# Optocoupler_Interface.net
KiCad netlist of a schematic drawn in Altium Designer
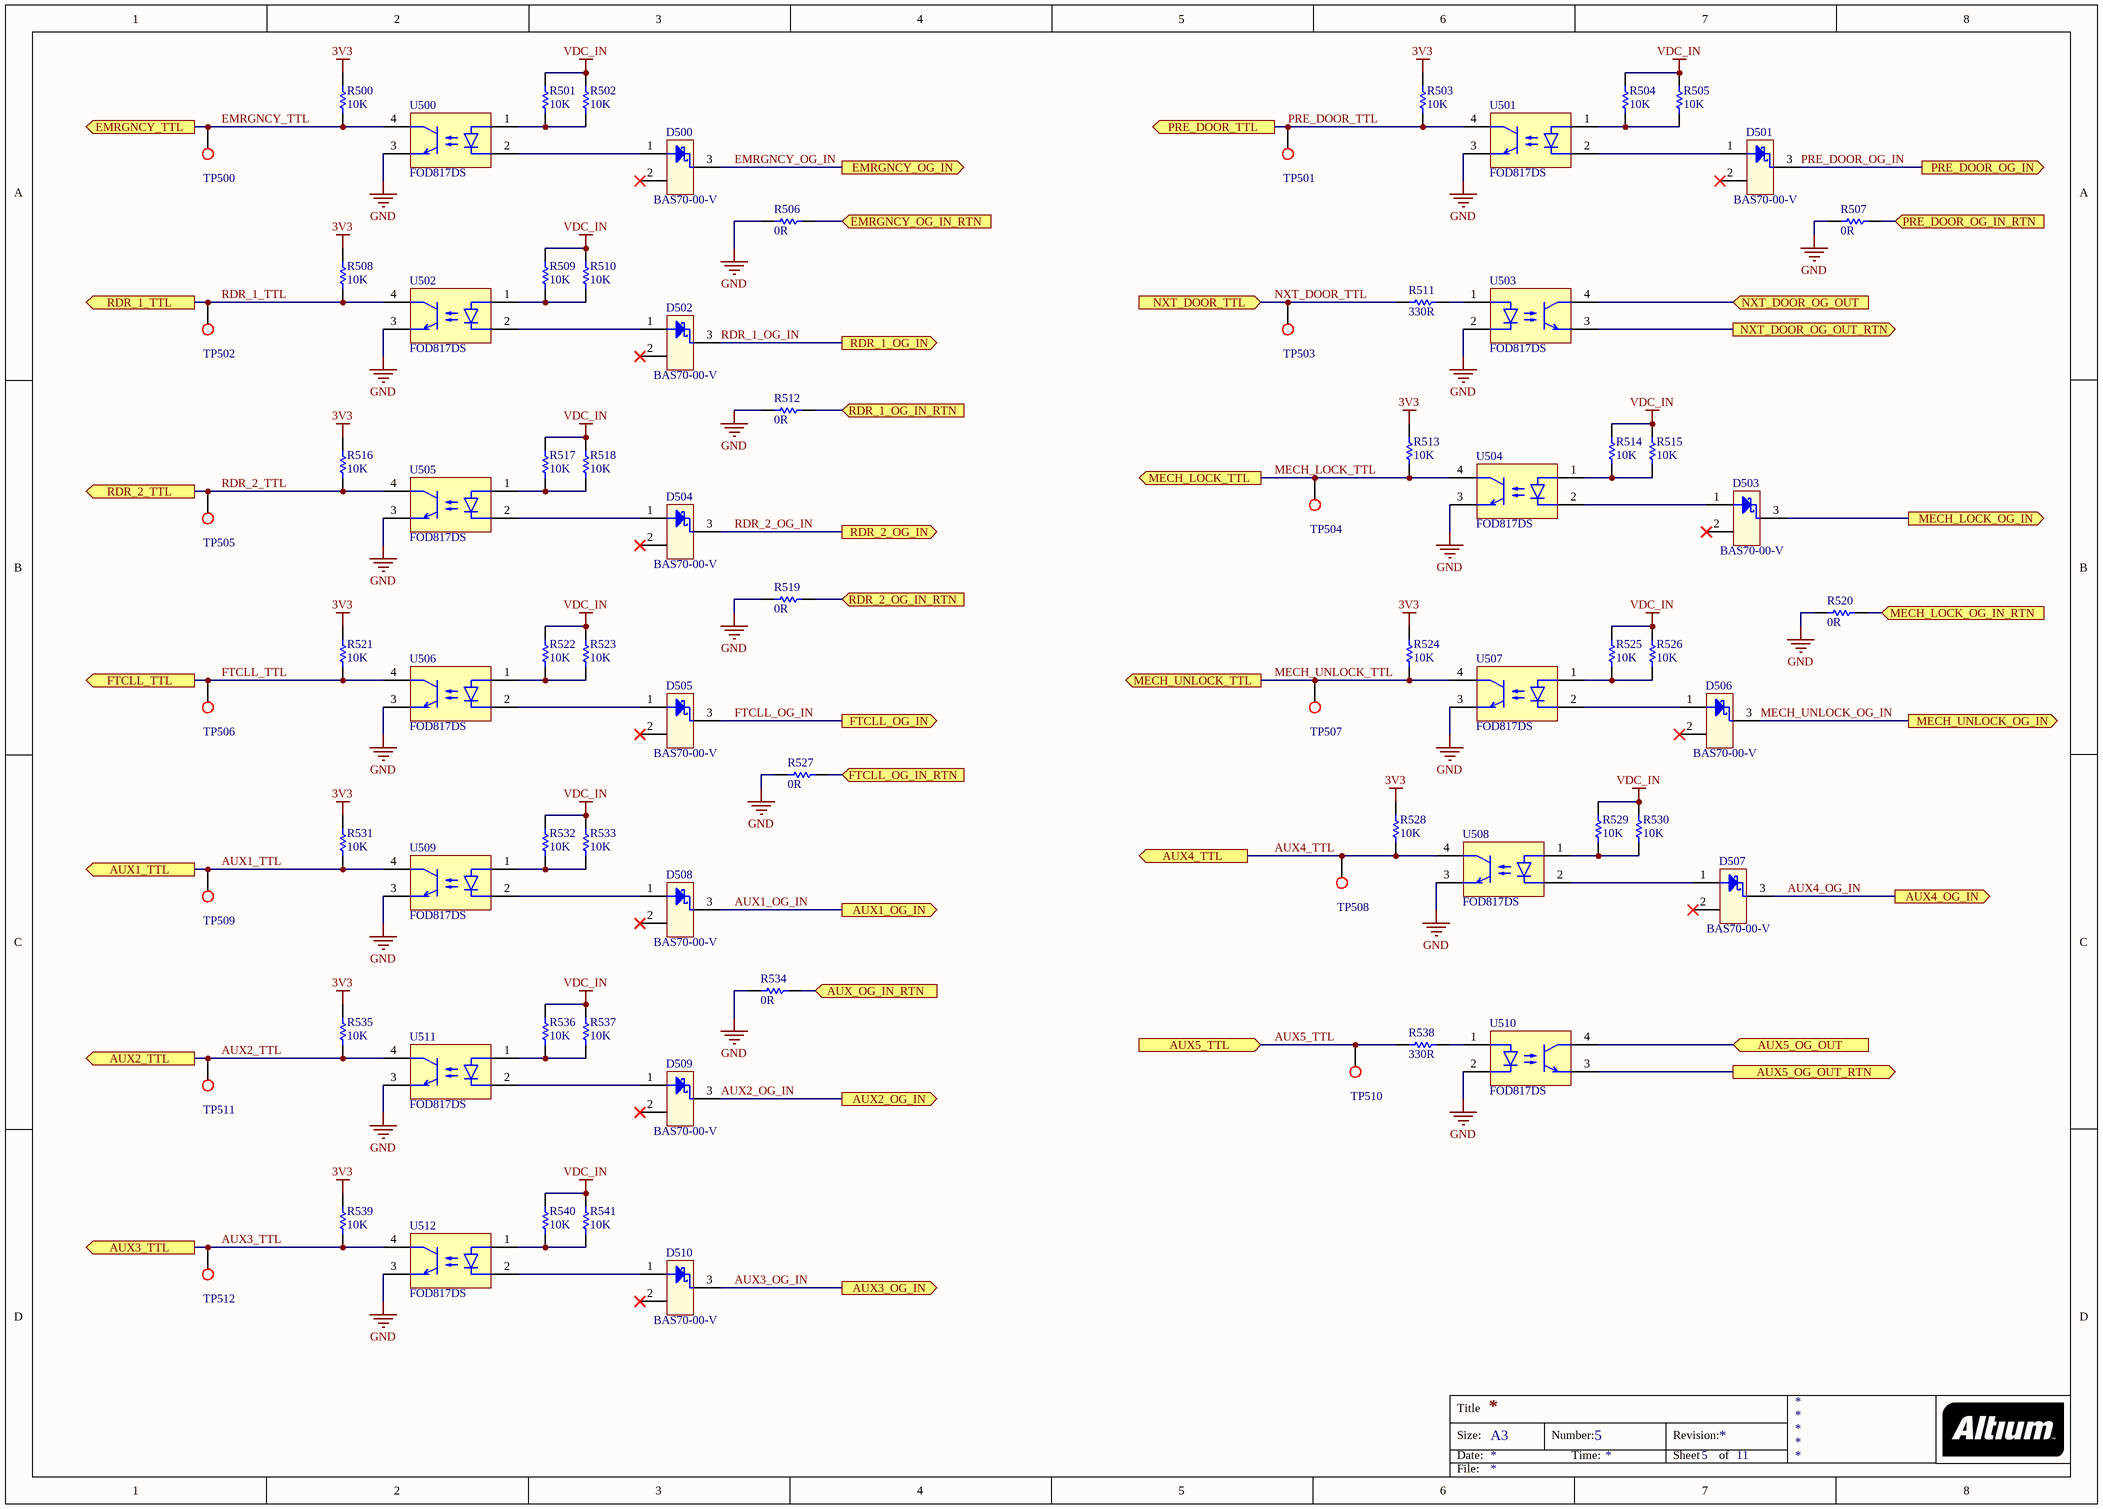
[diagram p0: Optocoupler_Interface.SchDoc]

(export (version "E")
  (design (tool "Eeschema 10.0.6"))
  (components
    (comp (ref "D500")
      (value "BAS70-00-V")
      (footprint "SOT90P247X115-3N")
      (description "Diode, Schottky, 0.41V @1mA, BAS70-00-V, SOT23")
      (fields (field (name "MANUFACTURER") "VISHAY"))
      (libsource (lib "Anime_Semiconductor") (part "AS15-820M-SI20-0002"))
    )
    (comp (ref "D501")
      (value "BAS70-00-V")
      (footprint "SOT90P247X115-3N")
      (description "Diode, Schottky, 0.41V @1mA, BAS70-00-V, SOT23")
      (fields (field (name "MANUFACTURER") "VISHAY"))
      (libsource (lib "Anime_Semiconductor") (part "AS15-820M-SI20-0002"))
    )
    (comp (ref "D502")
      (value "BAS70-00-V")
      (footprint "SOT90P247X115-3N")
      (description "Diode, Schottky, 0.41V @1mA, BAS70-00-V, SOT23")
      (fields (field (name "MANUFACTURER") "VISHAY"))
      (libsource (lib "Anime_Semiconductor") (part "AS15-820M-SI20-0002"))
    )
    (comp (ref "D503")
      (value "BAS70-00-V")
      (footprint "SOT90P247X115-3N")
      (description "Diode, Schottky, 0.41V @1mA, BAS70-00-V, SOT23")
      (fields (field (name "MANUFACTURER") "VISHAY"))
      (libsource (lib "Anime_Semiconductor") (part "AS15-820M-SI20-0002"))
    )
    (comp (ref "D504")
      (value "BAS70-00-V")
      (footprint "SOT90P247X115-3N")
      (description "Diode, Schottky, 0.41V @1mA, BAS70-00-V, SOT23")
      (fields (field (name "MANUFACTURER") "VISHAY"))
      (libsource (lib "Anime_Semiconductor") (part "AS15-820M-SI20-0002"))
    )
    (comp (ref "D505")
      (value "BAS70-00-V")
      (footprint "SOT90P247X115-3N")
      (description "Diode, Schottky, 0.41V @1mA, BAS70-00-V, SOT23")
      (fields (field (name "MANUFACTURER") "VISHAY"))
      (libsource (lib "Anime_Semiconductor") (part "AS15-820M-SI20-0002"))
    )
    (comp (ref "D506")
      (value "BAS70-00-V")
      (footprint "SOT90P247X115-3N")
      (description "Diode, Schottky, 0.41V @1mA, BAS70-00-V, SOT23")
      (fields (field (name "MANUFACTURER") "VISHAY"))
      (libsource (lib "Anime_Semiconductor") (part "AS15-820M-SI20-0002"))
    )
    (comp (ref "D507")
      (value "BAS70-00-V")
      (footprint "SOT90P247X115-3N")
      (description "Diode, Schottky, 0.41V @1mA, BAS70-00-V, SOT23")
      (fields (field (name "MANUFACTURER") "VISHAY"))
      (libsource (lib "Anime_Semiconductor") (part "AS15-820M-SI20-0002"))
    )
    (comp (ref "D508")
      (value "BAS70-00-V")
      (footprint "SOT90P247X115-3N")
      (description "Diode, Schottky, 0.41V @1mA, BAS70-00-V, SOT23")
      (fields (field (name "MANUFACTURER") "VISHAY"))
      (libsource (lib "Anime_Semiconductor") (part "AS15-820M-SI20-0002"))
    )
    (comp (ref "D509")
      (value "BAS70-00-V")
      (footprint "SOT90P247X115-3N")
      (description "Diode, Schottky, 0.41V @1mA, BAS70-00-V, SOT23")
      (fields (field (name "MANUFACTURER") "VISHAY"))
      (libsource (lib "Anime_Semiconductor") (part "AS15-820M-SI20-0002"))
    )
    (comp (ref "D510")
      (value "BAS70-00-V")
      (footprint "SOT90P247X115-3N")
      (description "Diode, Schottky, 0.41V @1mA, BAS70-00-V, SOT23")
      (fields (field (name "MANUFACTURER") "VISHAY"))
      (libsource (lib "Anime_Semiconductor") (part "AS15-820M-SI20-0002"))
    )
    (comp (ref "R500")
      (value "10K")
      (footprint "RESC1005X04N")
      (description "RES, E24, Thick Film, SMD, 10K, 1%, 0.1W, 0402")
      (fields
        (field (name "MANUFACTURER") "Panasonic")
        (field (name "MANUFACTURER PART NUMBER") "ERJ-2RKF1002X")
      )
      (libsource (lib "Anime_Resistor") (part "AR19-4100-S2B2-0000"))
    )
    (comp (ref "R501")
      (value "10K")
      (footprint "RESC2012X07N")
      (description "RES, E24, Thick Film, SMD, 10K, 1%, 0.125W, 0805")
      (fields
        (field (name "MANUFACTURER") "Panasonic")
        (field (name "MANUFACTURER PART NUMBER") "ERJ-6ENF1002V")
      )
      (libsource (lib "Anime_Resistor") (part "AR19-4100-S4B2-0000"))
    )
    (comp (ref "R502")
      (value "10K")
      (footprint "RESC2012X07N")
      (description "RES, E24, Thick Film, SMD, 10K, 1%, 0.125W, 0805")
      (fields
        (field (name "MANUFACTURER") "Panasonic")
        (field (name "MANUFACTURER PART NUMBER") "ERJ-6ENF1002V")
      )
      (libsource (lib "Anime_Resistor") (part "AR19-4100-S4B2-0000"))
    )
    (comp (ref "R503")
      (value "10K")
      (footprint "RESC1005X04N")
      (description "RES, E24, Thick Film, SMD, 10K, 1%, 0.1W, 0402")
      (fields
        (field (name "MANUFACTURER") "Panasonic")
        (field (name "MANUFACTURER PART NUMBER") "ERJ-2RKF1002X")
      )
      (libsource (lib "Anime_Resistor") (part "AR19-4100-S2B2-0000"))
    )
    (comp (ref "R504")
      (value "10K")
      (footprint "RESC2012X07N")
      (description "RES, E24, Thick Film, SMD, 10K, 1%, 0.125W, 0805")
      (fields
        (field (name "MANUFACTURER") "Panasonic")
        (field (name "MANUFACTURER PART NUMBER") "ERJ-6ENF1002V")
      )
      (libsource (lib "Anime_Resistor") (part "AR19-4100-S4B2-0000"))
    )
    (comp (ref "R505")
      (value "10K")
      (footprint "RESC2012X07N")
      (description "RES, E24, Thick Film, SMD, 10K, 1%, 0.125W, 0805")
      (fields
        (field (name "MANUFACTURER") "Panasonic")
        (field (name "MANUFACTURER PART NUMBER") "ERJ-6ENF1002V")
      )
      (libsource (lib "Anime_Resistor") (part "AR19-4100-S4B2-0000"))
    )
    (comp (ref "R506")
      (value "0R")
      (footprint "RESC2012X07N")
      (description "RES, Thick Film, SMD, 0R, Jumper, 0.125W, 0805")
      (fields
        (field (name "MANUFACTURER") "Panasonic")
        (field (name "MANUFACTURER PART NUMBER") "ERJ-6GEY0R00V")
      )
      (libsource (lib "Anime_Resistor") (part "AR19-0000-S407-0000"))
    )
    (comp (ref "R507")
      (value "0R")
      (footprint "RESC2012X07N")
      (description "RES, Thick Film, SMD, 0R, Jumper, 0.125W, 0805")
      (fields
        (field (name "MANUFACTURER") "Panasonic")
        (field (name "MANUFACTURER PART NUMBER") "ERJ-6GEY0R00V")
      )
      (libsource (lib "Anime_Resistor") (part "AR19-0000-S407-0000"))
    )
    (comp (ref "R508")
      (value "10K")
      (footprint "RESC1005X04N")
      (description "RES, E24, Thick Film, SMD, 10K, 1%, 0.1W, 0402")
      (fields
        (field (name "MANUFACTURER") "Panasonic")
        (field (name "MANUFACTURER PART NUMBER") "ERJ-2RKF1002X")
      )
      (libsource (lib "Anime_Resistor") (part "AR19-4100-S2B2-0000"))
    )
    (comp (ref "R509")
      (value "10K")
      (footprint "RESC2012X07N")
      (description "RES, E24, Thick Film, SMD, 10K, 1%, 0.125W, 0805")
      (fields
        (field (name "MANUFACTURER") "Panasonic")
        (field (name "MANUFACTURER PART NUMBER") "ERJ-6ENF1002V")
      )
      (libsource (lib "Anime_Resistor") (part "AR19-4100-S4B2-0000"))
    )
    (comp (ref "R510")
      (value "10K")
      (footprint "RESC2012X07N")
      (description "RES, E24, Thick Film, SMD, 10K, 1%, 0.125W, 0805")
      (fields
        (field (name "MANUFACTURER") "Panasonic")
        (field (name "MANUFACTURER PART NUMBER") "ERJ-6ENF1002V")
      )
      (libsource (lib "Anime_Resistor") (part "AR19-4100-S4B2-0000"))
    )
    (comp (ref "R511")
      (value "330R")
      (footprint "RESC1005X04N")
      (description "RES, E24, Thick Film, SMD, 330R, 1%, 0.1W, 0402")
      (fields
        (field (name "MANUFACTURER") "Panasonic")
        (field (name "MANUFACTURER PART NUMBER") "ERJ-2RKF3300X")
      )
      (libsource (lib "Anime_Resistor") (part "AR19-2330-S2B2-0000"))
    )
    (comp (ref "R512")
      (value "0R")
      (footprint "RESC2012X07N")
      (description "RES, Thick Film, SMD, 0R, Jumper, 0.125W, 0805")
      (fields
        (field (name "MANUFACTURER") "Panasonic")
        (field (name "MANUFACTURER PART NUMBER") "ERJ-6GEY0R00V")
      )
      (libsource (lib "Anime_Resistor") (part "AR19-0000-S407-0000"))
    )
    (comp (ref "R513")
      (value "10K")
      (footprint "RESC1005X04N")
      (description "RES, E24, Thick Film, SMD, 10K, 1%, 0.1W, 0402")
      (fields
        (field (name "MANUFACTURER") "Panasonic")
        (field (name "MANUFACTURER PART NUMBER") "ERJ-2RKF1002X")
      )
      (libsource (lib "Anime_Resistor") (part "AR19-4100-S2B2-0000"))
    )
    (comp (ref "R514")
      (value "10K")
      (footprint "RESC2012X07N")
      (description "RES, E24, Thick Film, SMD, 10K, 1%, 0.125W, 0805")
      (fields
        (field (name "MANUFACTURER") "Panasonic")
        (field (name "MANUFACTURER PART NUMBER") "ERJ-6ENF1002V")
      )
      (libsource (lib "Anime_Resistor") (part "AR19-4100-S4B2-0000"))
    )
    (comp (ref "R515")
      (value "10K")
      (footprint "RESC2012X07N")
      (description "RES, E24, Thick Film, SMD, 10K, 1%, 0.125W, 0805")
      (fields
        (field (name "MANUFACTURER") "Panasonic")
        (field (name "MANUFACTURER PART NUMBER") "ERJ-6ENF1002V")
      )
      (libsource (lib "Anime_Resistor") (part "AR19-4100-S4B2-0000"))
    )
    (comp (ref "R516")
      (value "10K")
      (footprint "RESC1005X04N")
      (description "RES, E24, Thick Film, SMD, 10K, 1%, 0.1W, 0402")
      (fields
        (field (name "MANUFACTURER") "Panasonic")
        (field (name "MANUFACTURER PART NUMBER") "ERJ-2RKF1002X")
      )
      (libsource (lib "Anime_Resistor") (part "AR19-4100-S2B2-0000"))
    )
    (comp (ref "R517")
      (value "10K")
      (footprint "RESC2012X07N")
      (description "RES, E24, Thick Film, SMD, 10K, 1%, 0.125W, 0805")
      (fields
        (field (name "MANUFACTURER") "Panasonic")
        (field (name "MANUFACTURER PART NUMBER") "ERJ-6ENF1002V")
      )
      (libsource (lib "Anime_Resistor") (part "AR19-4100-S4B2-0000"))
    )
    (comp (ref "R518")
      (value "10K")
      (footprint "RESC2012X07N")
      (description "RES, E24, Thick Film, SMD, 10K, 1%, 0.125W, 0805")
      (fields
        (field (name "MANUFACTURER") "Panasonic")
        (field (name "MANUFACTURER PART NUMBER") "ERJ-6ENF1002V")
      )
      (libsource (lib "Anime_Resistor") (part "AR19-4100-S4B2-0000"))
    )
    (comp (ref "R519")
      (value "0R")
      (footprint "RESC2012X07N")
      (description "RES, Thick Film, SMD, 0R, Jumper, 0.125W, 0805")
      (fields
        (field (name "MANUFACTURER") "Panasonic")
        (field (name "MANUFACTURER PART NUMBER") "ERJ-6GEY0R00V")
      )
      (libsource (lib "Anime_Resistor") (part "AR19-0000-S407-0000"))
    )
    (comp (ref "R520")
      (value "0R")
      (footprint "RESC2012X07N")
      (description "RES, Thick Film, SMD, 0R, Jumper, 0.125W, 0805")
      (fields
        (field (name "MANUFACTURER") "Panasonic")
        (field (name "MANUFACTURER PART NUMBER") "ERJ-6GEY0R00V")
      )
      (libsource (lib "Anime_Resistor") (part "AR19-0000-S407-0000"))
    )
    (comp (ref "R521")
      (value "10K")
      (footprint "RESC1005X04N")
      (description "RES, E24, Thick Film, SMD, 10K, 1%, 0.1W, 0402")
      (fields
        (field (name "MANUFACTURER") "Panasonic")
        (field (name "MANUFACTURER PART NUMBER") "ERJ-2RKF1002X")
      )
      (libsource (lib "Anime_Resistor") (part "AR19-4100-S2B2-0000"))
    )
    (comp (ref "R522")
      (value "10K")
      (footprint "RESC2012X07N")
      (description "RES, E24, Thick Film, SMD, 10K, 1%, 0.125W, 0805")
      (fields
        (field (name "MANUFACTURER") "Panasonic")
        (field (name "MANUFACTURER PART NUMBER") "ERJ-6ENF1002V")
      )
      (libsource (lib "Anime_Resistor") (part "AR19-4100-S4B2-0000"))
    )
    (comp (ref "R523")
      (value "10K")
      (footprint "RESC2012X07N")
      (description "RES, E24, Thick Film, SMD, 10K, 1%, 0.125W, 0805")
      (fields
        (field (name "MANUFACTURER") "Panasonic")
        (field (name "MANUFACTURER PART NUMBER") "ERJ-6ENF1002V")
      )
      (libsource (lib "Anime_Resistor") (part "AR19-4100-S4B2-0000"))
    )
    (comp (ref "R524")
      (value "10K")
      (footprint "RESC1005X04N")
      (description "RES, E24, Thick Film, SMD, 10K, 1%, 0.1W, 0402")
      (fields
        (field (name "MANUFACTURER") "Panasonic")
        (field (name "MANUFACTURER PART NUMBER") "ERJ-2RKF1002X")
      )
      (libsource (lib "Anime_Resistor") (part "AR19-4100-S2B2-0000"))
    )
    (comp (ref "R525")
      (value "10K")
      (footprint "RESC2012X07N")
      (description "RES, E24, Thick Film, SMD, 10K, 1%, 0.125W, 0805")
      (fields
        (field (name "MANUFACTURER") "Panasonic")
        (field (name "MANUFACTURER PART NUMBER") "ERJ-6ENF1002V")
      )
      (libsource (lib "Anime_Resistor") (part "AR19-4100-S4B2-0000"))
    )
    (comp (ref "R526")
      (value "10K")
      (footprint "RESC2012X07N")
      (description "RES, E24, Thick Film, SMD, 10K, 1%, 0.125W, 0805")
      (fields
        (field (name "MANUFACTURER") "Panasonic")
        (field (name "MANUFACTURER PART NUMBER") "ERJ-6ENF1002V")
      )
      (libsource (lib "Anime_Resistor") (part "AR19-4100-S4B2-0000"))
    )
    (comp (ref "R527")
      (value "0R")
      (footprint "RESC2012X07N")
      (description "RES, Thick Film, SMD, 0R, Jumper, 0.125W, 0805")
      (fields
        (field (name "MANUFACTURER") "Panasonic")
        (field (name "MANUFACTURER PART NUMBER") "ERJ-6GEY0R00V")
      )
      (libsource (lib "Anime_Resistor") (part "AR19-0000-S407-0000"))
    )
    (comp (ref "R528")
      (value "10K")
      (footprint "RESC1005X04N")
      (description "RES, E24, Thick Film, SMD, 10K, 1%, 0.1W, 0402")
      (fields
        (field (name "MANUFACTURER") "Panasonic")
        (field (name "MANUFACTURER PART NUMBER") "ERJ-2RKF1002X")
      )
      (libsource (lib "Anime_Resistor") (part "AR19-4100-S2B2-0000"))
    )
    (comp (ref "R529")
      (value "10K")
      (footprint "RESC2012X07N")
      (description "RES, E24, Thick Film, SMD, 10K, 1%, 0.125W, 0805")
      (fields
        (field (name "MANUFACTURER") "Panasonic")
        (field (name "MANUFACTURER PART NUMBER") "ERJ-6ENF1002V")
      )
      (libsource (lib "Anime_Resistor") (part "AR19-4100-S4B2-0000"))
    )
    (comp (ref "R530")
      (value "10K")
      (footprint "RESC2012X07N")
      (description "RES, E24, Thick Film, SMD, 10K, 1%, 0.125W, 0805")
      (fields
        (field (name "MANUFACTURER") "Panasonic")
        (field (name "MANUFACTURER PART NUMBER") "ERJ-6ENF1002V")
      )
      (libsource (lib "Anime_Resistor") (part "AR19-4100-S4B2-0000"))
    )
    (comp (ref "R531")
      (value "10K")
      (footprint "RESC1005X04N")
      (description "RES, E24, Thick Film, SMD, 10K, 1%, 0.1W, 0402")
      (fields
        (field (name "MANUFACTURER") "Panasonic")
        (field (name "MANUFACTURER PART NUMBER") "ERJ-2RKF1002X")
      )
      (libsource (lib "Anime_Resistor") (part "AR19-4100-S2B2-0000"))
    )
    (comp (ref "R532")
      (value "10K")
      (footprint "RESC2012X07N")
      (description "RES, E24, Thick Film, SMD, 10K, 1%, 0.125W, 0805")
      (fields
        (field (name "MANUFACTURER") "Panasonic")
        (field (name "MANUFACTURER PART NUMBER") "ERJ-6ENF1002V")
      )
      (libsource (lib "Anime_Resistor") (part "AR19-4100-S4B2-0000"))
    )
    (comp (ref "R533")
      (value "10K")
      (footprint "RESC2012X07N")
      (description "RES, E24, Thick Film, SMD, 10K, 1%, 0.125W, 0805")
      (fields
        (field (name "MANUFACTURER") "Panasonic")
        (field (name "MANUFACTURER PART NUMBER") "ERJ-6ENF1002V")
      )
      (libsource (lib "Anime_Resistor") (part "AR19-4100-S4B2-0000"))
    )
    (comp (ref "R534")
      (value "0R")
      (footprint "RESC2012X07N")
      (description "RES, Thick Film, SMD, 0R, Jumper, 0.125W, 0805")
      (fields
        (field (name "MANUFACTURER") "Panasonic")
        (field (name "MANUFACTURER PART NUMBER") "ERJ-6GEY0R00V")
      )
      (libsource (lib "Anime_Resistor") (part "AR19-0000-S407-0000"))
    )
    (comp (ref "R535")
      (value "10K")
      (footprint "RESC1005X04N")
      (description "RES, E24, Thick Film, SMD, 10K, 1%, 0.1W, 0402")
      (fields
        (field (name "MANUFACTURER") "Panasonic")
        (field (name "MANUFACTURER PART NUMBER") "ERJ-2RKF1002X")
      )
      (libsource (lib "Anime_Resistor") (part "AR19-4100-S2B2-0000"))
    )
    (comp (ref "R536")
      (value "10K")
      (footprint "RESC2012X07N")
      (description "RES, E24, Thick Film, SMD, 10K, 1%, 0.125W, 0805")
      (fields
        (field (name "MANUFACTURER") "Panasonic")
        (field (name "MANUFACTURER PART NUMBER") "ERJ-6ENF1002V")
      )
      (libsource (lib "Anime_Resistor") (part "AR19-4100-S4B2-0000"))
    )
    (comp (ref "R537")
      (value "10K")
      (footprint "RESC2012X07N")
      (description "RES, E24, Thick Film, SMD, 10K, 1%, 0.125W, 0805")
      (fields
        (field (name "MANUFACTURER") "Panasonic")
        (field (name "MANUFACTURER PART NUMBER") "ERJ-6ENF1002V")
      )
      (libsource (lib "Anime_Resistor") (part "AR19-4100-S4B2-0000"))
    )
    (comp (ref "R538")
      (value "330R")
      (footprint "RESC1005X04N")
      (description "RES, E24, Thick Film, SMD, 330R, 1%, 0.1W, 0402")
      (fields
        (field (name "MANUFACTURER") "Panasonic")
        (field (name "MANUFACTURER PART NUMBER") "ERJ-2RKF3300X")
      )
      (libsource (lib "Anime_Resistor") (part "AR19-2330-S2B2-0000"))
    )
    (comp (ref "R539")
      (value "10K")
      (footprint "RESC1005X04N")
      (description "RES, E24, Thick Film, SMD, 10K, 1%, 0.1W, 0402")
      (fields
        (field (name "MANUFACTURER") "Panasonic")
        (field (name "MANUFACTURER PART NUMBER") "ERJ-2RKF1002X")
      )
      (libsource (lib "Anime_Resistor") (part "AR19-4100-S2B2-0000"))
    )
    (comp (ref "R540")
      (value "10K")
      (footprint "RESC2012X07N")
      (description "RES, E24, Thick Film, SMD, 10K, 1%, 0.125W, 0805")
      (fields
        (field (name "MANUFACTURER") "Panasonic")
        (field (name "MANUFACTURER PART NUMBER") "ERJ-6ENF1002V")
      )
      (libsource (lib "Anime_Resistor") (part "AR19-4100-S4B2-0000"))
    )
    (comp (ref "R541")
      (value "10K")
      (footprint "RESC2012X07N")
      (description "RES, E24, Thick Film, SMD, 10K, 1%, 0.125W, 0805")
      (fields
        (field (name "MANUFACTURER") "Panasonic")
        (field (name "MANUFACTURER PART NUMBER") "ERJ-6ENF1002V")
      )
      (libsource (lib "Anime_Resistor") (part "AR19-4100-S4B2-0000"))
    )
    (comp (ref "TP500")
      (value "AEMT-C00S-1000-0000")
      (footprint "TP100")
      (description "Test Point, Circular, 1mm")
      (libsource (lib "Anime_Electromechanical") (part "AEMT-C00S-1000-0000"))
    )
    (comp (ref "TP501")
      (value "AEMT-C00S-1000-0000")
      (footprint "TP100")
      (description "Test Point, Circular, 1mm")
      (libsource (lib "Anime_Electromechanical") (part "AEMT-C00S-1000-0000"))
    )
    (comp (ref "TP502")
      (value "AEMT-C00S-1000-0000")
      (footprint "TP100")
      (description "Test Point, Circular, 1mm")
      (libsource (lib "Anime_Electromechanical") (part "AEMT-C00S-1000-0000"))
    )
    (comp (ref "TP503")
      (value "AEMT-C00S-1000-0000")
      (footprint "TP100")
      (description "Test Point, Circular, 1mm")
      (libsource (lib "Anime_Electromechanical") (part "AEMT-C00S-1000-0000"))
    )
    (comp (ref "TP504")
      (value "AEMT-C00S-1000-0000")
      (footprint "TP100")
      (description "Test Point, Circular, 1mm")
      (libsource (lib "Anime_Electromechanical") (part "AEMT-C00S-1000-0000"))
    )
    (comp (ref "TP505")
      (value "AEMT-C00S-1000-0000")
      (footprint "TP100")
      (description "Test Point, Circular, 1mm")
      (libsource (lib "Anime_Electromechanical") (part "AEMT-C00S-1000-0000"))
    )
    (comp (ref "TP506")
      (value "AEMT-C00S-1000-0000")
      (footprint "TP100")
      (description "Test Point, Circular, 1mm")
      (libsource (lib "Anime_Electromechanical") (part "AEMT-C00S-1000-0000"))
    )
    (comp (ref "TP507")
      (value "AEMT-C00S-1000-0000")
      (footprint "TP100")
      (description "Test Point, Circular, 1mm")
      (libsource (lib "Anime_Electromechanical") (part "AEMT-C00S-1000-0000"))
    )
    (comp (ref "TP508")
      (value "AEMT-C00S-1000-0000")
      (footprint "TP100")
      (description "Test Point, Circular, 1mm")
      (libsource (lib "Anime_Electromechanical") (part "AEMT-C00S-1000-0000"))
    )
    (comp (ref "TP509")
      (value "AEMT-C00S-1000-0000")
      (footprint "TP100")
      (description "Test Point, Circular, 1mm")
      (libsource (lib "Anime_Electromechanical") (part "AEMT-C00S-1000-0000"))
    )
    (comp (ref "TP510")
      (value "AEMT-C00S-1000-0000")
      (footprint "TP100")
      (description "Test Point, Circular, 1mm")
      (libsource (lib "Anime_Electromechanical") (part "AEMT-C00S-1000-0000"))
    )
    (comp (ref "TP511")
      (value "AEMT-C00S-1000-0000")
      (footprint "TP100")
      (description "Test Point, Circular, 1mm")
      (libsource (lib "Anime_Electromechanical") (part "AEMT-C00S-1000-0000"))
    )
    (comp (ref "TP512")
      (value "AEMT-C00S-1000-0000")
      (footprint "TP100")
      (description "Test Point, Circular, 1mm")
      (libsource (lib "Anime_Electromechanical") (part "AEMT-C00S-1000-0000"))
    )
    (comp (ref "U500")
      (value "FOD817DS")
      (footprint "SOP254P1020X400-4N")
      (description "Optocoupler, Phototransistor Output, Single Channel, CTR 300-600%, 5000V Isolation")
      (fields (field (name "MANUFACTURER") "Fairchild"))
      (libsource (lib "") (part "ASB1-850M-SM61-0000_1"))
    )
    (comp (ref "U501")
      (value "FOD817DS")
      (footprint "SOP254P1020X400-4N")
      (description "Optocoupler, Phototransistor Output, Single Channel, CTR 300-600%, 5000V Isolation")
      (fields (field (name "MANUFACTURER") "Fairchild"))
      (libsource (lib "") (part "ASB1-850M-SM61-0000_1"))
    )
    (comp (ref "U502")
      (value "FOD817DS")
      (footprint "SOP254P1020X400-4N")
      (description "Optocoupler, Phototransistor Output, Single Channel, CTR 300-600%, 5000V Isolation")
      (fields (field (name "MANUFACTURER") "Fairchild"))
      (libsource (lib "") (part "ASB1-850M-SM61-0000_1"))
    )
    (comp (ref "U503")
      (value "FOD817DS")
      (footprint "SOP254P1020X400-4N")
      (description "Optocoupler, Phototransistor Output, Single Channel, CTR 300-600%, 5000V Isolation")
      (fields (field (name "MANUFACTURER") "Fairchild"))
      (libsource (lib "Anime_Semiconductor") (part "ASB1-850M-SM61-0000"))
    )
    (comp (ref "U504")
      (value "FOD817DS")
      (footprint "SOP254P1020X400-4N")
      (description "Optocoupler, Phototransistor Output, Single Channel, CTR 300-600%, 5000V Isolation")
      (fields (field (name "MANUFACTURER") "Fairchild"))
      (libsource (lib "") (part "ASB1-850M-SM61-0000_1"))
    )
    (comp (ref "U505")
      (value "FOD817DS")
      (footprint "SOP254P1020X400-4N")
      (description "Optocoupler, Phototransistor Output, Single Channel, CTR 300-600%, 5000V Isolation")
      (fields (field (name "MANUFACTURER") "Fairchild"))
      (libsource (lib "") (part "ASB1-850M-SM61-0000_1"))
    )
    (comp (ref "U506")
      (value "FOD817DS")
      (footprint "SOP254P1020X400-4N")
      (description "Optocoupler, Phototransistor Output, Single Channel, CTR 300-600%, 5000V Isolation")
      (fields (field (name "MANUFACTURER") "Fairchild"))
      (libsource (lib "") (part "ASB1-850M-SM61-0000_1"))
    )
    (comp (ref "U507")
      (value "FOD817DS")
      (footprint "SOP254P1020X400-4N")
      (description "Optocoupler, Phototransistor Output, Single Channel, CTR 300-600%, 5000V Isolation")
      (fields (field (name "MANUFACTURER") "Fairchild"))
      (libsource (lib "") (part "ASB1-850M-SM61-0000_1"))
    )
    (comp (ref "U508")
      (value "FOD817DS")
      (footprint "SOP254P1020X400-4N")
      (description "Optocoupler, Phototransistor Output, Single Channel, CTR 300-600%, 5000V Isolation")
      (fields (field (name "MANUFACTURER") "Fairchild"))
      (libsource (lib "") (part "ASB1-850M-SM61-0000_1"))
    )
    (comp (ref "U509")
      (value "FOD817DS")
      (footprint "SOP254P1020X400-4N")
      (description "Optocoupler, Phototransistor Output, Single Channel, CTR 300-600%, 5000V Isolation")
      (fields (field (name "MANUFACTURER") "Fairchild"))
      (libsource (lib "") (part "ASB1-850M-SM61-0000_1"))
    )
    (comp (ref "U510")
      (value "FOD817DS")
      (footprint "SOP254P1020X400-4N")
      (description "Optocoupler, Phototransistor Output, Single Channel, CTR 300-600%, 5000V Isolation")
      (fields (field (name "MANUFACTURER") "Fairchild"))
      (libsource (lib "Anime_Semiconductor") (part "ASB1-850M-SM61-0000"))
    )
    (comp (ref "U511")
      (value "FOD817DS")
      (footprint "SOP254P1020X400-4N")
      (description "Optocoupler, Phototransistor Output, Single Channel, CTR 300-600%, 5000V Isolation")
      (fields (field (name "MANUFACTURER") "Fairchild"))
      (libsource (lib "") (part "ASB1-850M-SM61-0000_1"))
    )
    (comp (ref "U512")
      (value "FOD817DS")
      (footprint "SOP254P1020X400-4N")
      (description "Optocoupler, Phototransistor Output, Single Channel, CTR 300-600%, 5000V Isolation")
      (fields (field (name "MANUFACTURER") "Fairchild"))
      (libsource (lib "") (part "ASB1-850M-SM61-0000_1"))
    )
  )
  (nets
    (net (code "1") (name "/AUX1_OG_IN") (class "Default")
      (node (ref "D508") (pin "3") (pinfunction "3_3") (pintype "passive"))
    )
    (net (code "2") (name "/AUX1_TTL") (class "Default")
      (node (ref "R531") (pin "1") (pinfunction "1_1") (pintype "passive"))
      (node (ref "TP509") (pin "1") (pintype "passive"))
      (node (ref "U509") (pin "4") (pinfunction "C1_4") (pintype "passive"))
    )
    (net (code "3") (name "/AUX2_OG_IN") (class "Default")
      (node (ref "D509") (pin "3") (pinfunction "3_3") (pintype "passive"))
    )
    (net (code "4") (name "/AUX2_TTL") (class "Default")
      (node (ref "R535") (pin "1") (pinfunction "1_1") (pintype "passive"))
      (node (ref "TP511") (pin "1") (pintype "passive"))
      (node (ref "U511") (pin "4") (pinfunction "C1_4") (pintype "passive"))
    )
    (net (code "5") (name "/AUX3_OG_IN") (class "Default")
      (node (ref "D510") (pin "3") (pinfunction "3_3") (pintype "passive"))
    )
    (net (code "6") (name "/AUX3_TTL") (class "Default")
      (node (ref "R539") (pin "1") (pinfunction "1_1") (pintype "passive"))
      (node (ref "TP512") (pin "1") (pintype "passive"))
      (node (ref "U512") (pin "4") (pinfunction "C1_4") (pintype "passive"))
    )
    (net (code "7") (name "/AUX4_OG_IN") (class "Default")
      (node (ref "D507") (pin "3") (pinfunction "3_3") (pintype "passive"))
    )
    (net (code "8") (name "/AUX4_TTL") (class "Default")
      (node (ref "R528") (pin "1") (pinfunction "1_1") (pintype "passive"))
      (node (ref "TP508") (pin "1") (pintype "passive"))
      (node (ref "U508") (pin "4") (pinfunction "C1_4") (pintype "passive"))
    )
    (net (code "9") (name "/AUX5_OG_OUT") (class "Default")
      (node (ref "U510") (pin "4") (pinfunction "C1_4") (pintype "passive"))
    )
    (net (code "10") (name "/AUX5_OG_OUT_RTN") (class "Default")
      (node (ref "U510") (pin "3") (pinfunction "E1_3") (pintype "passive"))
    )
    (net (code "11") (name "/AUX5_TTL") (class "Default")
      (node (ref "R538") (pin "1") (pinfunction "1_1") (pintype "passive"))
      (node (ref "TP510") (pin "1") (pintype "passive"))
    )
    (net (code "12") (name "/AUX_OG_IN_RTN") (class "Default")
      (node (ref "R534") (pin "1") (pinfunction "1_1") (pintype "passive"))
    )
    (net (code "13") (name "/EMRGNCY_OG_IN") (class "Default")
      (node (ref "D500") (pin "3") (pinfunction "3_3") (pintype "passive"))
    )
    (net (code "14") (name "/EMRGNCY_OG_IN_RTN") (class "Default")
      (node (ref "R506") (pin "2") (pinfunction "2_2") (pintype "passive"))
    )
    (net (code "15") (name "/EMRGNCY_TTL") (class "Default")
      (node (ref "R500") (pin "1") (pinfunction "1_1") (pintype "passive"))
      (node (ref "TP500") (pin "1") (pintype "passive"))
      (node (ref "U500") (pin "4") (pinfunction "C1_4") (pintype "passive"))
    )
    (net (code "16") (name "/FTCLL_OG_IN") (class "Default")
      (node (ref "D505") (pin "3") (pinfunction "3_3") (pintype "passive"))
    )
    (net (code "17") (name "/FTCLL_OG_IN_RTN") (class "Default")
      (node (ref "R527") (pin "2") (pinfunction "2_2") (pintype "passive"))
    )
    (net (code "18") (name "/FTCLL_TTL") (class "Default")
      (node (ref "R521") (pin "1") (pinfunction "1_1") (pintype "passive"))
      (node (ref "TP506") (pin "1") (pintype "passive"))
      (node (ref "U506") (pin "4") (pinfunction "C1_4") (pintype "passive"))
    )
    (net (code "19") (name "/MECH_LOCK_OG_IN") (class "Default")
      (node (ref "D503") (pin "3") (pinfunction "3_3") (pintype "passive"))
    )
    (net (code "20") (name "/MECH_LOCK_OG_IN_RTN") (class "Default")
      (node (ref "R520") (pin "1") (pinfunction "1_1") (pintype "passive"))
    )
    (net (code "21") (name "/MECH_LOCK_TTL") (class "Default")
      (node (ref "R513") (pin "1") (pinfunction "1_1") (pintype "passive"))
      (node (ref "TP504") (pin "1") (pintype "passive"))
      (node (ref "U504") (pin "4") (pinfunction "C1_4") (pintype "passive"))
    )
    (net (code "22") (name "/MECH_UNLOCK_OG_IN") (class "Default")
      (node (ref "D506") (pin "3") (pinfunction "3_3") (pintype "passive"))
    )
    (net (code "23") (name "/MECH_UNLOCK_TTL") (class "Default")
      (node (ref "R524") (pin "1") (pinfunction "1_1") (pintype "passive"))
      (node (ref "TP507") (pin "1") (pintype "passive"))
      (node (ref "U507") (pin "4") (pinfunction "C1_4") (pintype "passive"))
    )
    (net (code "24") (name "/NXT_DOOR_OG_OUT") (class "Default")
      (node (ref "U503") (pin "4") (pinfunction "C1_4") (pintype "passive"))
    )
    (net (code "25") (name "/NXT_DOOR_OG_OUT_RTN") (class "Default")
      (node (ref "U503") (pin "3") (pinfunction "E1_3") (pintype "passive"))
    )
    (net (code "26") (name "/NXT_DOOR_TTL") (class "Default")
      (node (ref "R511") (pin "1") (pinfunction "1_1") (pintype "passive"))
      (node (ref "TP503") (pin "1") (pintype "passive"))
    )
    (net (code "27") (name "/PRE_DOOR_OG_IN") (class "Default")
      (node (ref "D501") (pin "3") (pinfunction "3_3") (pintype "passive"))
    )
    (net (code "28") (name "/PRE_DOOR_OG_IN_RTN") (class "Default")
      (node (ref "R507") (pin "1") (pinfunction "1_1") (pintype "passive"))
    )
    (net (code "29") (name "/PRE_DOOR_TTL") (class "Default")
      (node (ref "R503") (pin "1") (pinfunction "1_1") (pintype "passive"))
      (node (ref "TP501") (pin "1") (pintype "passive"))
      (node (ref "U501") (pin "4") (pinfunction "C1_4") (pintype "passive"))
    )
    (net (code "30") (name "/RDR_1_OG_IN") (class "Default")
      (node (ref "D502") (pin "3") (pinfunction "3_3") (pintype "passive"))
    )
    (net (code "31") (name "/RDR_1_OG_IN_RTN") (class "Default")
      (node (ref "R512") (pin "2") (pinfunction "2_2") (pintype "passive"))
    )
    (net (code "32") (name "/RDR_1_TTL") (class "Default")
      (node (ref "R508") (pin "1") (pinfunction "1_1") (pintype "passive"))
      (node (ref "TP502") (pin "1") (pintype "passive"))
      (node (ref "U502") (pin "4") (pinfunction "C1_4") (pintype "passive"))
    )
    (net (code "33") (name "/RDR_2_OG_IN") (class "Default")
      (node (ref "D504") (pin "3") (pinfunction "3_3") (pintype "passive"))
    )
    (net (code "34") (name "/RDR_2_OG_IN_RTN") (class "Default")
      (node (ref "R519") (pin "2") (pinfunction "2_2") (pintype "passive"))
    )
    (net (code "35") (name "/RDR_2_TTL") (class "Default")
      (node (ref "R516") (pin "1") (pinfunction "1_1") (pintype "passive"))
      (node (ref "TP505") (pin "1") (pintype "passive"))
      (node (ref "U505") (pin "4") (pinfunction "C1_4") (pintype "passive"))
    )
    (net (code "36") (name "3V3") (class "Default")
      (node (ref "R500") (pin "2") (pinfunction "2_2") (pintype "passive"))
      (node (ref "R503") (pin "2") (pinfunction "2_2") (pintype "passive"))
      (node (ref "R508") (pin "2") (pinfunction "2_2") (pintype "passive"))
      (node (ref "R513") (pin "2") (pinfunction "2_2") (pintype "passive"))
      (node (ref "R516") (pin "2") (pinfunction "2_2") (pintype "passive"))
      (node (ref "R521") (pin "2") (pinfunction "2_2") (pintype "passive"))
      (node (ref "R524") (pin "2") (pinfunction "2_2") (pintype "passive"))
      (node (ref "R528") (pin "2") (pinfunction "2_2") (pintype "passive"))
      (node (ref "R531") (pin "2") (pinfunction "2_2") (pintype "passive"))
      (node (ref "R535") (pin "2") (pinfunction "2_2") (pintype "passive"))
      (node (ref "R539") (pin "2") (pinfunction "2_2") (pintype "passive"))
    )
    (net (code "37") (name "GND") (class "Default")
      (node (ref "R506") (pin "1") (pinfunction "1_1") (pintype "passive"))
      (node (ref "R507") (pin "2") (pinfunction "2_2") (pintype "passive"))
      (node (ref "R512") (pin "1") (pinfunction "1_1") (pintype "passive"))
      (node (ref "R519") (pin "1") (pinfunction "1_1") (pintype "passive"))
      (node (ref "R520") (pin "2") (pinfunction "2_2") (pintype "passive"))
      (node (ref "R527") (pin "1") (pinfunction "1_1") (pintype "passive"))
      (node (ref "R534") (pin "2") (pinfunction "2_2") (pintype "passive"))
      (node (ref "U500") (pin "3") (pinfunction "E1_3") (pintype "passive"))
      (node (ref "U501") (pin "3") (pinfunction "E1_3") (pintype "passive"))
      (node (ref "U502") (pin "3") (pinfunction "E1_3") (pintype "passive"))
      (node (ref "U503") (pin "2") (pinfunction "K1_2") (pintype "passive"))
      (node (ref "U504") (pin "3") (pinfunction "E1_3") (pintype "passive"))
      (node (ref "U505") (pin "3") (pinfunction "E1_3") (pintype "passive"))
      (node (ref "U506") (pin "3") (pinfunction "E1_3") (pintype "passive"))
      (node (ref "U507") (pin "3") (pinfunction "E1_3") (pintype "passive"))
      (node (ref "U508") (pin "3") (pinfunction "E1_3") (pintype "passive"))
      (node (ref "U509") (pin "3") (pinfunction "E1_3") (pintype "passive"))
      (node (ref "U510") (pin "2") (pinfunction "K1_2") (pintype "passive"))
      (node (ref "U511") (pin "3") (pinfunction "E1_3") (pintype "passive"))
      (node (ref "U512") (pin "3") (pinfunction "E1_3") (pintype "passive"))
    )
    (net (code "38") (name "Net-(U500-A1)") (class "Default")
      (node (ref "R501") (pin "2") (pinfunction "2_2") (pintype "passive"))
      (node (ref "R502") (pin "2") (pinfunction "2_2") (pintype "passive"))
      (node (ref "U500") (pin "1") (pinfunction "A1_1") (pintype "passive"))
    )
    (net (code "39") (name "Net-(U500-K1)") (class "Default")
      (node (ref "D500") (pin "1") (pinfunction "1_1") (pintype "passive"))
      (node (ref "U500") (pin "2") (pinfunction "K1_2") (pintype "passive"))
    )
    (net (code "40") (name "Net-(U501-A1)") (class "Default")
      (node (ref "R504") (pin "2") (pinfunction "2_2") (pintype "passive"))
      (node (ref "R505") (pin "2") (pinfunction "2_2") (pintype "passive"))
      (node (ref "U501") (pin "1") (pinfunction "A1_1") (pintype "passive"))
    )
    (net (code "41") (name "Net-(U501-K1)") (class "Default")
      (node (ref "D501") (pin "1") (pinfunction "1_1") (pintype "passive"))
      (node (ref "U501") (pin "2") (pinfunction "K1_2") (pintype "passive"))
    )
    (net (code "42") (name "Net-(U502-A1)") (class "Default")
      (node (ref "R509") (pin "2") (pinfunction "2_2") (pintype "passive"))
      (node (ref "R510") (pin "2") (pinfunction "2_2") (pintype "passive"))
      (node (ref "U502") (pin "1") (pinfunction "A1_1") (pintype "passive"))
    )
    (net (code "43") (name "Net-(U502-K1)") (class "Default")
      (node (ref "D502") (pin "1") (pinfunction "1_1") (pintype "passive"))
      (node (ref "U502") (pin "2") (pinfunction "K1_2") (pintype "passive"))
    )
    (net (code "44") (name "Net-(U503-A1)") (class "Default")
      (node (ref "R511") (pin "2") (pinfunction "2_2") (pintype "passive"))
      (node (ref "U503") (pin "1") (pinfunction "A1_1") (pintype "passive"))
    )
    (net (code "45") (name "Net-(U504-A1)") (class "Default")
      (node (ref "R514") (pin "2") (pinfunction "2_2") (pintype "passive"))
      (node (ref "R515") (pin "2") (pinfunction "2_2") (pintype "passive"))
      (node (ref "U504") (pin "1") (pinfunction "A1_1") (pintype "passive"))
    )
    (net (code "46") (name "Net-(U504-K1)") (class "Default")
      (node (ref "D503") (pin "1") (pinfunction "1_1") (pintype "passive"))
      (node (ref "U504") (pin "2") (pinfunction "K1_2") (pintype "passive"))
    )
    (net (code "47") (name "Net-(U505-A1)") (class "Default")
      (node (ref "R517") (pin "2") (pinfunction "2_2") (pintype "passive"))
      (node (ref "R518") (pin "2") (pinfunction "2_2") (pintype "passive"))
      (node (ref "U505") (pin "1") (pinfunction "A1_1") (pintype "passive"))
    )
    (net (code "48") (name "Net-(U505-K1)") (class "Default")
      (node (ref "D504") (pin "1") (pinfunction "1_1") (pintype "passive"))
      (node (ref "U505") (pin "2") (pinfunction "K1_2") (pintype "passive"))
    )
    (net (code "49") (name "Net-(U506-A1)") (class "Default")
      (node (ref "R522") (pin "2") (pinfunction "2_2") (pintype "passive"))
      (node (ref "R523") (pin "2") (pinfunction "2_2") (pintype "passive"))
      (node (ref "U506") (pin "1") (pinfunction "A1_1") (pintype "passive"))
    )
    (net (code "50") (name "Net-(U506-K1)") (class "Default")
      (node (ref "D505") (pin "1") (pinfunction "1_1") (pintype "passive"))
      (node (ref "U506") (pin "2") (pinfunction "K1_2") (pintype "passive"))
    )
    (net (code "51") (name "Net-(U507-A1)") (class "Default")
      (node (ref "R525") (pin "2") (pinfunction "2_2") (pintype "passive"))
      (node (ref "R526") (pin "2") (pinfunction "2_2") (pintype "passive"))
      (node (ref "U507") (pin "1") (pinfunction "A1_1") (pintype "passive"))
    )
    (net (code "52") (name "Net-(U507-K1)") (class "Default")
      (node (ref "D506") (pin "1") (pinfunction "1_1") (pintype "passive"))
      (node (ref "U507") (pin "2") (pinfunction "K1_2") (pintype "passive"))
    )
    (net (code "53") (name "Net-(U508-A1)") (class "Default")
      (node (ref "R529") (pin "2") (pinfunction "2_2") (pintype "passive"))
      (node (ref "R530") (pin "2") (pinfunction "2_2") (pintype "passive"))
      (node (ref "U508") (pin "1") (pinfunction "A1_1") (pintype "passive"))
    )
    (net (code "54") (name "Net-(U508-K1)") (class "Default")
      (node (ref "D507") (pin "1") (pinfunction "1_1") (pintype "passive"))
      (node (ref "U508") (pin "2") (pinfunction "K1_2") (pintype "passive"))
    )
    (net (code "55") (name "Net-(U509-A1)") (class "Default")
      (node (ref "R532") (pin "2") (pinfunction "2_2") (pintype "passive"))
      (node (ref "R533") (pin "2") (pinfunction "2_2") (pintype "passive"))
      (node (ref "U509") (pin "1") (pinfunction "A1_1") (pintype "passive"))
    )
    (net (code "56") (name "Net-(U509-K1)") (class "Default")
      (node (ref "D508") (pin "1") (pinfunction "1_1") (pintype "passive"))
      (node (ref "U509") (pin "2") (pinfunction "K1_2") (pintype "passive"))
    )
    (net (code "57") (name "Net-(U510-A1)") (class "Default")
      (node (ref "R538") (pin "2") (pinfunction "2_2") (pintype "passive"))
      (node (ref "U510") (pin "1") (pinfunction "A1_1") (pintype "passive"))
    )
    (net (code "58") (name "Net-(U511-A1)") (class "Default")
      (node (ref "R536") (pin "2") (pinfunction "2_2") (pintype "passive"))
      (node (ref "R537") (pin "2") (pinfunction "2_2") (pintype "passive"))
      (node (ref "U511") (pin "1") (pinfunction "A1_1") (pintype "passive"))
    )
    (net (code "59") (name "Net-(U511-K1)") (class "Default")
      (node (ref "D509") (pin "1") (pinfunction "1_1") (pintype "passive"))
      (node (ref "U511") (pin "2") (pinfunction "K1_2") (pintype "passive"))
    )
    (net (code "60") (name "Net-(U512-A1)") (class "Default")
      (node (ref "R540") (pin "2") (pinfunction "2_2") (pintype "passive"))
      (node (ref "R541") (pin "2") (pinfunction "2_2") (pintype "passive"))
      (node (ref "U512") (pin "1") (pinfunction "A1_1") (pintype "passive"))
    )
    (net (code "61") (name "Net-(U512-K1)") (class "Default")
      (node (ref "D510") (pin "1") (pinfunction "1_1") (pintype "passive"))
      (node (ref "U512") (pin "2") (pinfunction "K1_2") (pintype "passive"))
    )
    (net (code "62") (name "VDC_IN") (class "Default")
      (node (ref "R501") (pin "1") (pinfunction "1_1") (pintype "passive"))
      (node (ref "R502") (pin "1") (pinfunction "1_1") (pintype "passive"))
      (node (ref "R504") (pin "1") (pinfunction "1_1") (pintype "passive"))
      (node (ref "R505") (pin "1") (pinfunction "1_1") (pintype "passive"))
      (node (ref "R509") (pin "1") (pinfunction "1_1") (pintype "passive"))
      (node (ref "R510") (pin "1") (pinfunction "1_1") (pintype "passive"))
      (node (ref "R514") (pin "1") (pinfunction "1_1") (pintype "passive"))
      (node (ref "R515") (pin "1") (pinfunction "1_1") (pintype "passive"))
      (node (ref "R517") (pin "1") (pinfunction "1_1") (pintype "passive"))
      (node (ref "R518") (pin "1") (pinfunction "1_1") (pintype "passive"))
      (node (ref "R522") (pin "1") (pinfunction "1_1") (pintype "passive"))
      (node (ref "R523") (pin "1") (pinfunction "1_1") (pintype "passive"))
      (node (ref "R525") (pin "1") (pinfunction "1_1") (pintype "passive"))
      (node (ref "R526") (pin "1") (pinfunction "1_1") (pintype "passive"))
      (node (ref "R529") (pin "1") (pinfunction "1_1") (pintype "passive"))
      (node (ref "R530") (pin "1") (pinfunction "1_1") (pintype "passive"))
      (node (ref "R532") (pin "1") (pinfunction "1_1") (pintype "passive"))
      (node (ref "R533") (pin "1") (pinfunction "1_1") (pintype "passive"))
      (node (ref "R536") (pin "1") (pinfunction "1_1") (pintype "passive"))
      (node (ref "R537") (pin "1") (pinfunction "1_1") (pintype "passive"))
      (node (ref "R540") (pin "1") (pinfunction "1_1") (pintype "passive"))
      (node (ref "R541") (pin "1") (pinfunction "1_1") (pintype "passive"))
    )
    (net (code "63") (name "unconnected-(D500-NC-Pad2)") (class "Default")
      (node (ref "D500") (pin "2") (pinfunction "NC_2") (pintype "passive+no_connect"))
    )
    (net (code "64") (name "unconnected-(D501-NC-Pad2)") (class "Default")
      (node (ref "D501") (pin "2") (pinfunction "NC_2") (pintype "passive+no_connect"))
    )
    (net (code "65") (name "unconnected-(D502-NC-Pad2)") (class "Default")
      (node (ref "D502") (pin "2") (pinfunction "NC_2") (pintype "passive+no_connect"))
    )
    (net (code "66") (name "unconnected-(D503-NC-Pad2)") (class "Default")
      (node (ref "D503") (pin "2") (pinfunction "NC_2") (pintype "passive+no_connect"))
    )
    (net (code "67") (name "unconnected-(D504-NC-Pad2)") (class "Default")
      (node (ref "D504") (pin "2") (pinfunction "NC_2") (pintype "passive+no_connect"))
    )
    (net (code "68") (name "unconnected-(D505-NC-Pad2)") (class "Default")
      (node (ref "D505") (pin "2") (pinfunction "NC_2") (pintype "passive+no_connect"))
    )
    (net (code "69") (name "unconnected-(D506-NC-Pad2)") (class "Default")
      (node (ref "D506") (pin "2") (pinfunction "NC_2") (pintype "passive+no_connect"))
    )
    (net (code "70") (name "unconnected-(D507-NC-Pad2)") (class "Default")
      (node (ref "D507") (pin "2") (pinfunction "NC_2") (pintype "passive+no_connect"))
    )
    (net (code "71") (name "unconnected-(D508-NC-Pad2)") (class "Default")
      (node (ref "D508") (pin "2") (pinfunction "NC_2") (pintype "passive+no_connect"))
    )
    (net (code "72") (name "unconnected-(D509-NC-Pad2)") (class "Default")
      (node (ref "D509") (pin "2") (pinfunction "NC_2") (pintype "passive+no_connect"))
    )
    (net (code "73") (name "unconnected-(D510-NC-Pad2)") (class "Default")
      (node (ref "D510") (pin "2") (pinfunction "NC_2") (pintype "passive+no_connect"))
    )
  )
)
